# dual_encoder_i2c_shield_revB.net
KiCad netlist of a schematic drawn in EAGLE
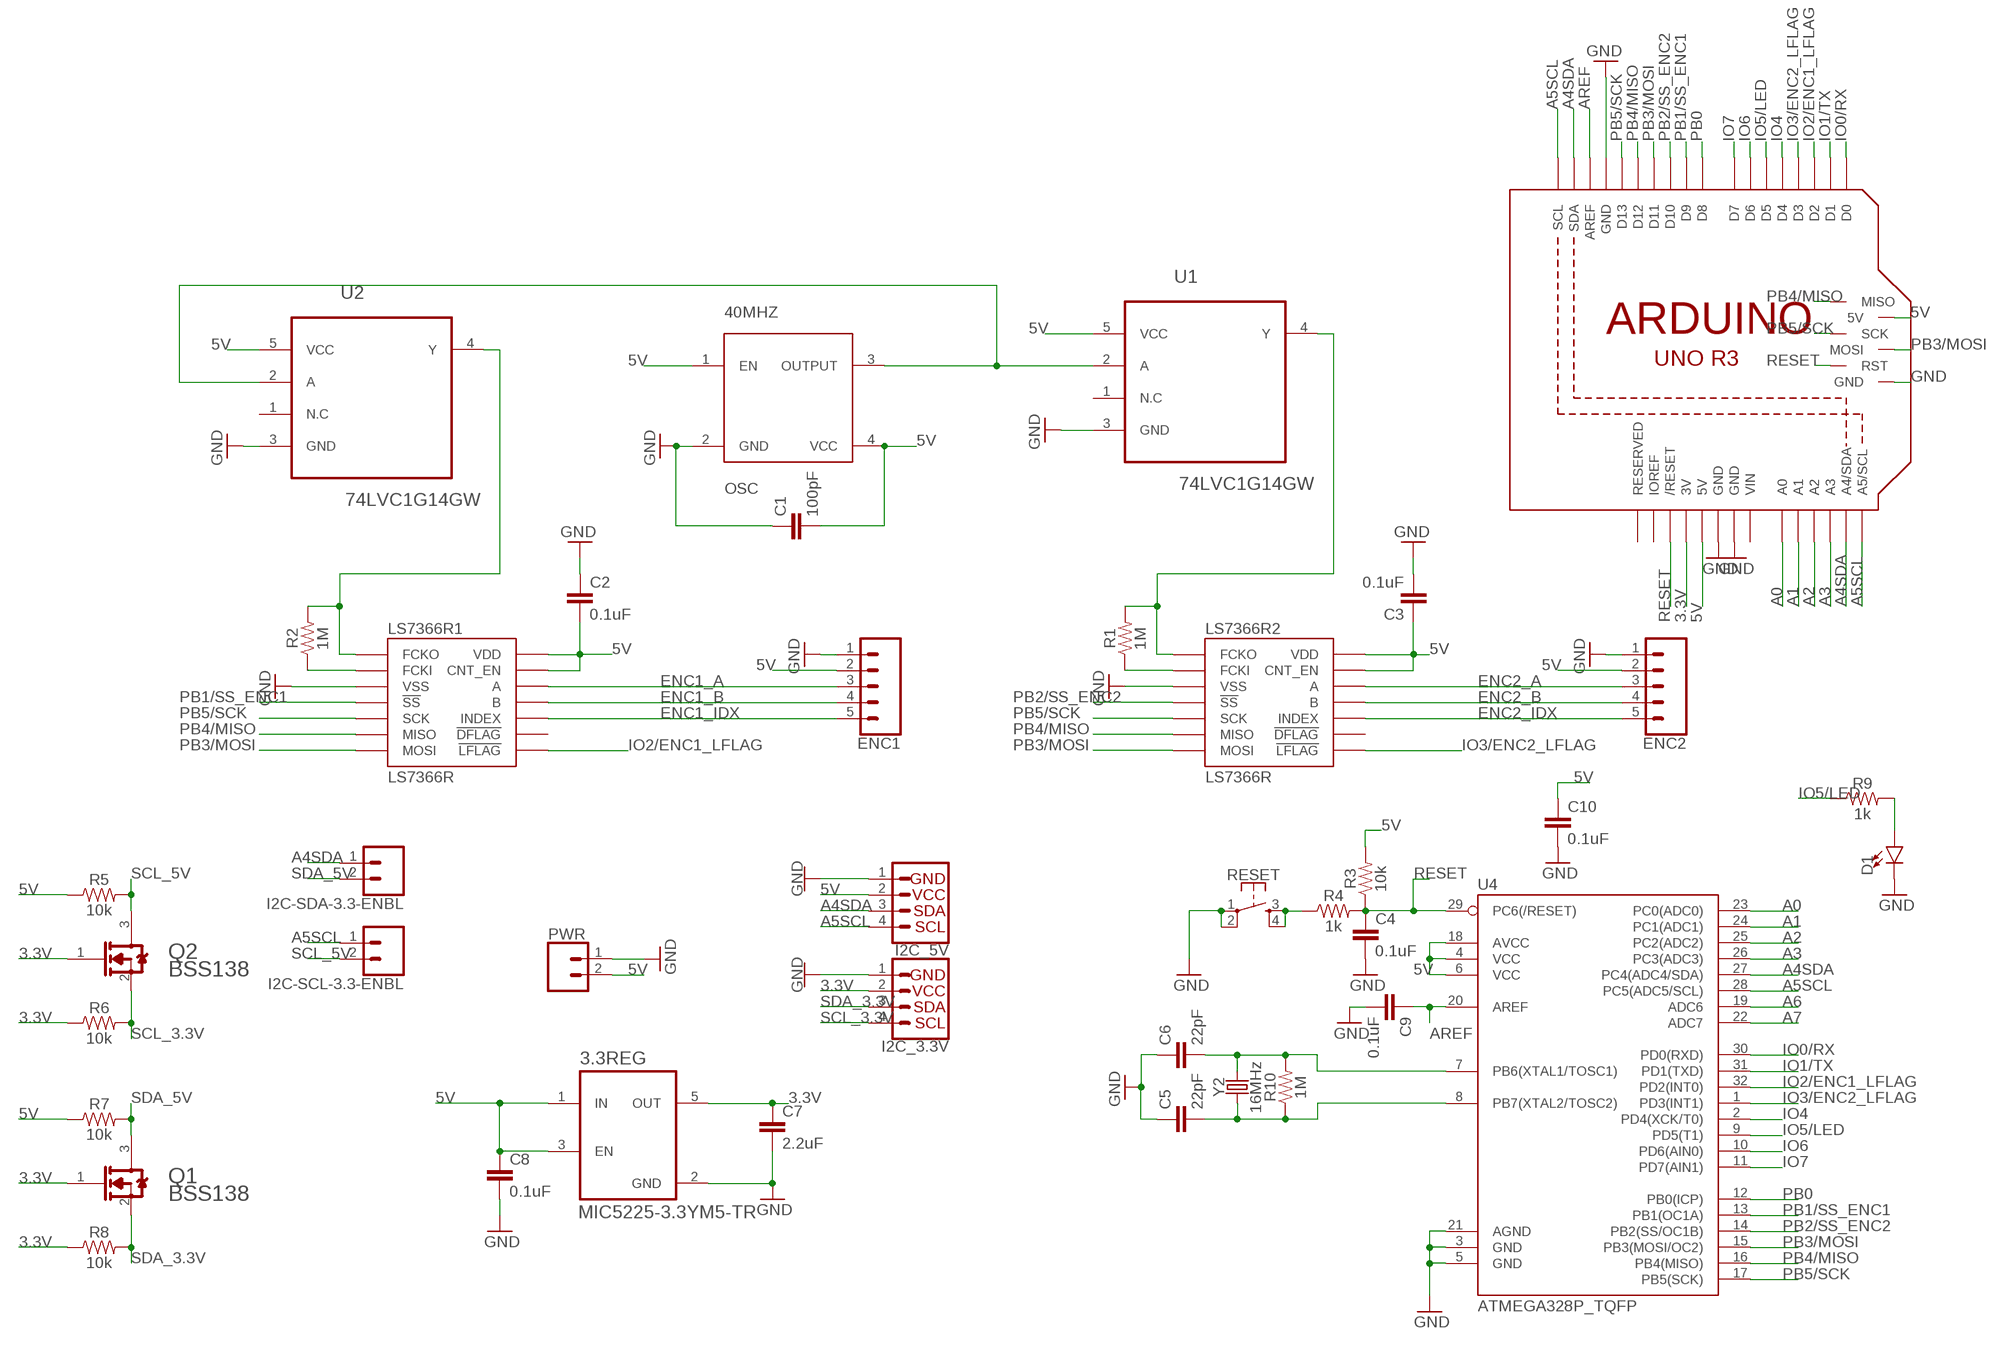
[diagram p0: schematic, sheet 1]

(export (version "E")
  (design (tool "Eeschema 10.0.6"))
  (components
    (comp (ref "3.3REG")
      (value "MIC5225-3.3YM5-TR")
      (footprint "eagle-import:SOT95P280X145-5N")
      (fields (field (name "MF") "Microchip"))
      (libsource (lib "eagle-import") (part "MIC5225-3.3YM5-TR"))
    )
    (comp (ref "40MHZ")
      (value "OSC")
      (footprint "eagle-import:CB3OSCILLATOR")
      (libsource (lib "eagle-import") (part "OSC"))
    )
    (comp (ref "C1")
      (value "100pF")
      (footprint "eagle-import:0603")
      (libsource (lib "eagle-import") (part "100PF-0603-50V-5%"))
    )
    (comp (ref "C2")
      (value "0.1uF")
      (footprint "eagle-import:0603")
      (libsource (lib "eagle-import") (part "0.1UF-0603-25V-5%"))
    )
    (comp (ref "C3")
      (value "0.1uF")
      (footprint "eagle-import:0603")
      (libsource (lib "eagle-import") (part "0.1UF-0603-25V-5%"))
    )
    (comp (ref "C4")
      (value "0.1uF")
      (footprint "eagle-import:0603")
      (libsource (lib "eagle-import") (part "0.1UF-0603-25V-5%"))
    )
    (comp (ref "C5")
      (value "22pF")
      (footprint "eagle-import:0603")
      (libsource (lib "eagle-import") (part "22PF-0603-50V-5%"))
    )
    (comp (ref "C6")
      (value "22pF")
      (footprint "eagle-import:0603")
      (libsource (lib "eagle-import") (part "22PF-0603-50V-5%"))
    )
    (comp (ref "C7")
      (value "2.2uF")
      (footprint "eagle-import:0603")
      (libsource (lib "eagle-import") (part "2.2UF-0603-10V-20%"))
    )
    (comp (ref "C8")
      (value "0.1uF")
      (footprint "eagle-import:0603")
      (libsource (lib "eagle-import") (part "0.1UF-0603-25V-5%"))
    )
    (comp (ref "C9")
      (value "0.1uF")
      (footprint "eagle-import:0603")
      (libsource (lib "eagle-import") (part "0.1UF-0603-25V-5%"))
    )
    (comp (ref "C10")
      (value "0.1uF")
      (footprint "eagle-import:0603")
      (libsource (lib "eagle-import") (part "0.1UF-0603-25V-5%"))
    )
    (comp (ref "D1")
      (value "LED0603")
      (footprint "eagle-import:LED-0603")
      (libsource (lib "eagle-import") (part "LED0603"))
    )
    (comp (ref "ENC1")
      (value "CONN_05")
      (footprint "eagle-import:1X05")
      (libsource (lib "eagle-import") (part "CONN_05"))
    )
    (comp (ref "ENC2")
      (value "CONN_05")
      (footprint "eagle-import:1X05")
      (libsource (lib "eagle-import") (part "CONN_05"))
    )
    (comp (ref "I2C-SCL-3.3-ENBL")
      (value "CONN_02")
      (footprint "eagle-import:1X02")
      (libsource (lib "eagle-import") (part "CONN_02"))
    )
    (comp (ref "I2C-SDA-3.3-ENBL")
      (value "CONN_02")
      (footprint "eagle-import:1X02")
      (libsource (lib "eagle-import") (part "CONN_02"))
    )
    (comp (ref "I2C_3.3V")
      (value "QWIIC_CONNECTORJS-1MM")
      (footprint "eagle-import:JST04_1MM_RA")
      (libsource (lib "eagle-import") (part "QWIIC_CONNECTORJS-1MM"))
    )
    (comp (ref "I2C_5V")
      (value "QWIIC_CONNECTORJS-1MM")
      (footprint "eagle-import:JST04_1MM_RA")
      (libsource (lib "eagle-import") (part "QWIIC_CONNECTORJS-1MM"))
    )
    (comp (ref "LS7366R1")
      (value "LS7366R")
      (footprint "eagle-import:SOIC14")
      (fields (field (name "MF") "LSI"))
      (libsource (lib "eagle-import") (part "LS7366R"))
    )
    (comp (ref "LS7366R2")
      (value "LS7366R")
      (footprint "eagle-import:SOIC14")
      (fields (field (name "MF") "LSI"))
      (libsource (lib "eagle-import") (part "LS7366R"))
    )
    (comp (ref "M1")
      (value "ARDUINO_R3_ICSP")
      (footprint "eagle-import:ARDUINOR3_ICSP")
      (libsource (lib "eagle-import") (part "ARDUINO_R3_ICSP"))
    )
    (comp (ref "PWR")
      (value "CONN_02-JST-2MM-SMT")
      (footprint "eagle-import:JST-2-SMD")
      (libsource (lib "eagle-import") (part "CONN_02-JST-2MM-SMT"))
    )
    (comp (ref "Q1")
      (value "ON_SEMI_BSS138ON_SEMI_BSS138_0_0")
      (footprint "eagle-import:ON_SEMI_BSS138_0")
      (fields
        (field (name "DIGIKEY_PART_NUMBER") "BSS138CT-ND")
        (field (name "MF") "ON Semi")
        (field (name "MOUSER_PART_NUMBER") "512-BSS138")
      )
      (libsource (lib "eagle-import") (part "ON_SEMI_BSS138ON_SEMI_BSS138_0_0"))
    )
    (comp (ref "Q2")
      (value "ON_SEMI_BSS138ON_SEMI_BSS138_0_0")
      (footprint "eagle-import:ON_SEMI_BSS138_0")
      (fields
        (field (name "DIGIKEY_PART_NUMBER") "BSS138CT-ND")
        (field (name "MF") "ON Semi")
        (field (name "MOUSER_PART_NUMBER") "512-BSS138")
      )
      (libsource (lib "eagle-import") (part "ON_SEMI_BSS138ON_SEMI_BSS138_0_0"))
    )
    (comp (ref "R1")
      (value "1M")
      (footprint "eagle-import:0603")
      (libsource (lib "eagle-import") (part "1MOHM-0603-1/4W-5%"))
    )
    (comp (ref "R2")
      (value "1M")
      (footprint "eagle-import:0603")
      (libsource (lib "eagle-import") (part "1MOHM-0603-1/4W-5%"))
    )
    (comp (ref "R3")
      (value "10k")
      (footprint "eagle-import:0603")
      (libsource (lib "eagle-import") (part "10KOHM-0603-1/10W-1%"))
    )
    (comp (ref "R4")
      (value "1k")
      (footprint "eagle-import:0603")
      (libsource (lib "eagle-import") (part "1KOHM-0603-1/10W-1%"))
    )
    (comp (ref "R5")
      (value "10k")
      (footprint "eagle-import:0603")
      (libsource (lib "eagle-import") (part "10KOHM-0603-1/10W-1%"))
    )
    (comp (ref "R6")
      (value "10k")
      (footprint "eagle-import:0603")
      (libsource (lib "eagle-import") (part "10KOHM-0603-1/10W-1%"))
    )
    (comp (ref "R7")
      (value "10k")
      (footprint "eagle-import:0603")
      (libsource (lib "eagle-import") (part "10KOHM-0603-1/10W-1%"))
    )
    (comp (ref "R8")
      (value "10k")
      (footprint "eagle-import:0603")
      (libsource (lib "eagle-import") (part "10KOHM-0603-1/10W-1%"))
    )
    (comp (ref "R9")
      (value "1k")
      (footprint "eagle-import:0603")
      (libsource (lib "eagle-import") (part "1KOHM-0603-1/10W-1%"))
    )
    (comp (ref "R10")
      (value "1M")
      (footprint "eagle-import:0603")
      (libsource (lib "eagle-import") (part "1MOHM-0603-1/4W-5%"))
    )
    (comp (ref "RESET")
      (value "MOMENTARY-SWITCH-SPST-2-SMD-5.2MM")
      (footprint "eagle-import:TACTILE_SWITCH_SMD_5.2MM")
      (libsource (lib "eagle-import") (part "MOMENTARY-SWITCH-SPST-2-SMD-5.2MM"))
    )
    (comp (ref "U1")
      (value "74LVC1G14GW")
      (footprint "eagle-import:SOT65P210X110-5N")
      (fields (field (name "MF") "NXP Semiconductors"))
      (libsource (lib "eagle-import") (part "74LVC1G14GW"))
    )
    (comp (ref "U2")
      (value "74LVC1G14GW")
      (footprint "eagle-import:SOT65P210X110-5N")
      (fields (field (name "MF") "NXP Semiconductors"))
      (libsource (lib "eagle-import") (part "74LVC1G14GW"))
    )
    (comp (ref "U4")
      (value "ATMEGA328P_TQFP")
      (footprint "eagle-import:TQFP32-08")
      (libsource (lib "eagle-import") (part "ATMEGA328P_TQFP"))
    )
    (comp (ref "Y2")
      (value "16MHz")
      (footprint "eagle-import:CRYSTAL-SMD-5X3.2-4PAD")
      (libsource (lib "eagle-import") (part "CRYSTAL-16MHZSMD-5X3.2"))
    )
  )
  (nets
    (net (code "1") (name "/3.3V") (class "Default")
      (node (ref "3.3REG") (pin "5") (pinfunction "OUT_5") (pintype "output"))
      (node (ref "C7") (pin "1") (pinfunction "1_1") (pintype "passive"))
      (node (ref "I2C_3.3V") (pin "2") (pinfunction "2_2") (pintype "power_in"))
      (node (ref "M1") (pin "3V") (pinfunction "3V_3V") (pintype "power_in"))
      (node (ref "Q1") (pin "1") (pinfunction "G_1") (pintype "bidirectional"))
      (node (ref "Q2") (pin "1") (pinfunction "G_1") (pintype "bidirectional"))
      (node (ref "R6") (pin "1") (pinfunction "1_1") (pintype "passive"))
      (node (ref "R8") (pin "1") (pinfunction "1_1") (pintype "passive"))
    )
    (net (code "2") (name "/5V") (class "Default")
      (node (ref "3.3REG") (pin "1") (pinfunction "IN_1") (pintype "input"))
      (node (ref "3.3REG") (pin "3") (pinfunction "EN_3") (pintype "input"))
      (node (ref "40MHZ") (pin "1") (pinfunction "EN_1") (pintype "input"))
      (node (ref "40MHZ") (pin "4") (pinfunction "VCC_4") (pintype "input"))
      (node (ref "C1") (pin "2") (pinfunction "2_2") (pintype "passive"))
      (node (ref "C10") (pin "1") (pinfunction "1_1") (pintype "passive"))
      (node (ref "C2") (pin "2") (pinfunction "2_2") (pintype "passive"))
      (node (ref "C3") (pin "1") (pinfunction "1_1") (pintype "passive"))
      (node (ref "C8") (pin "1") (pinfunction "1_1") (pintype "passive"))
      (node (ref "ENC1") (pin "2") (pinfunction "2_2") (pintype "passive"))
      (node (ref "ENC2") (pin "2") (pinfunction "2_2") (pintype "passive"))
      (node (ref "I2C_5V") (pin "2") (pinfunction "2_2") (pintype "power_in"))
      (node (ref "LS7366R1") (pin "13") (pinfunction "CNT_EN_13") (pintype "bidirectional"))
      (node (ref "LS7366R1") (pin "14") (pinfunction "VDD_14") (pintype "bidirectional"))
      (node (ref "LS7366R2") (pin "13") (pinfunction "CNT_EN_13") (pintype "bidirectional"))
      (node (ref "LS7366R2") (pin "14") (pinfunction "VDD_14") (pintype "bidirectional"))
      (node (ref "M1") (pin "5V") (pinfunction "5V_5V") (pintype "power_in"))
      (node (ref "M1") (pin "5V_ICSP") (pinfunction "5V_5V_ICSP") (pintype "passive"))
      (node (ref "PWR") (pin "2") (pinfunction "1_2") (pintype "passive"))
      (node (ref "R3") (pin "2") (pinfunction "2_2") (pintype "passive"))
      (node (ref "R5") (pin "1") (pinfunction "1_1") (pintype "passive"))
      (node (ref "R7") (pin "1") (pinfunction "1_1") (pintype "passive"))
      (node (ref "U1") (pin "5") (pinfunction "VCC_5") (pintype "power_in"))
      (node (ref "U2") (pin "5") (pinfunction "VCC_5") (pintype "power_in"))
      (node (ref "U4") (pin "18") (pinfunction "AVCC_18") (pintype "bidirectional"))
      (node (ref "U4") (pin "4") (pinfunction "VCC_4") (pintype "bidirectional"))
      (node (ref "U4") (pin "6") (pinfunction "VCC_6") (pintype "bidirectional"))
    )
    (net (code "3") (name "/A0") (class "Default")
      (node (ref "M1") (pin "A0") (pinfunction "A0_A0") (pintype "bidirectional"))
      (node (ref "U4") (pin "23") (pinfunction "PC0(ADC0)_23") (pintype "bidirectional"))
    )
    (net (code "4") (name "/A1") (class "Default")
      (node (ref "M1") (pin "A1") (pinfunction "A1_A1") (pintype "bidirectional"))
      (node (ref "U4") (pin "24") (pinfunction "PC1(ADC1)_24") (pintype "bidirectional"))
    )
    (net (code "5") (name "/A2") (class "Default")
      (node (ref "M1") (pin "A2") (pinfunction "A2_A2") (pintype "bidirectional"))
      (node (ref "U4") (pin "25") (pinfunction "PC2(ADC2)_25") (pintype "bidirectional"))
    )
    (net (code "6") (name "/A3") (class "Default")
      (node (ref "M1") (pin "A3") (pinfunction "A3_A3") (pintype "bidirectional"))
      (node (ref "U4") (pin "26") (pinfunction "PC3(ADC3)_26") (pintype "bidirectional"))
    )
    (net (code "7") (name "/A4SDA") (class "Default")
      (node (ref "I2C-SDA-3.3-ENBL") (pin "1") (pinfunction "1_1") (pintype "passive"))
      (node (ref "I2C_5V") (pin "3") (pinfunction "3_3") (pintype "passive"))
      (node (ref "M1") (pin "A4") (pinfunction "A4/SDA_A4") (pintype "bidirectional"))
      (node (ref "M1") (pin "SDA") (pinfunction "SDA_SDA") (pintype "bidirectional"))
      (node (ref "U4") (pin "27") (pinfunction "PC4(ADC4/SDA)_27") (pintype "bidirectional"))
    )
    (net (code "8") (name "/A5SCL") (class "Default")
      (node (ref "I2C-SCL-3.3-ENBL") (pin "1") (pinfunction "1_1") (pintype "passive"))
      (node (ref "I2C_5V") (pin "4") (pinfunction "4_4") (pintype "passive"))
      (node (ref "M1") (pin "A5") (pinfunction "A5/SCL_A5") (pintype "bidirectional"))
      (node (ref "M1") (pin "SCL") (pinfunction "SCL_SCL") (pintype "bidirectional"))
      (node (ref "U4") (pin "28") (pinfunction "PC5(ADC5/SCL)_28") (pintype "bidirectional"))
    )
    (net (code "9") (name "/A6") (class "Default")
      (node (ref "U4") (pin "19") (pinfunction "ADC6_19") (pintype "bidirectional"))
    )
    (net (code "10") (name "/A7") (class "Default")
      (node (ref "U4") (pin "22") (pinfunction "ADC7_22") (pintype "bidirectional"))
    )
    (net (code "11") (name "/AREF") (class "Default")
      (node (ref "C9") (pin "1") (pinfunction "1_1") (pintype "passive"))
      (node (ref "M1") (pin "AREF") (pinfunction "AREF_AREF") (pintype "bidirectional"))
      (node (ref "U4") (pin "20") (pinfunction "AREF_20") (pintype "bidirectional"))
    )
    (net (code "12") (name "/ENC1_A") (class "Default")
      (node (ref "ENC1") (pin "3") (pinfunction "3_3") (pintype "passive"))
      (node (ref "LS7366R1") (pin "12") (pinfunction "A_12") (pintype "bidirectional"))
    )
    (net (code "13") (name "/ENC1_B") (class "Default")
      (node (ref "ENC1") (pin "4") (pinfunction "4_4") (pintype "passive"))
      (node (ref "LS7366R1") (pin "11") (pinfunction "B_11") (pintype "bidirectional"))
    )
    (net (code "14") (name "/ENC1_IDX") (class "Default")
      (node (ref "ENC1") (pin "5") (pinfunction "5_5") (pintype "passive"))
      (node (ref "LS7366R1") (pin "10") (pinfunction "INDEX_10") (pintype "bidirectional"))
    )
    (net (code "15") (name "/ENC2_A") (class "Default")
      (node (ref "ENC2") (pin "3") (pinfunction "3_3") (pintype "passive"))
      (node (ref "LS7366R2") (pin "12") (pinfunction "A_12") (pintype "bidirectional"))
    )
    (net (code "16") (name "/ENC2_B") (class "Default")
      (node (ref "ENC2") (pin "4") (pinfunction "4_4") (pintype "passive"))
      (node (ref "LS7366R2") (pin "11") (pinfunction "B_11") (pintype "bidirectional"))
    )
    (net (code "17") (name "/ENC2_IDX") (class "Default")
      (node (ref "ENC2") (pin "5") (pinfunction "5_5") (pintype "passive"))
      (node (ref "LS7366R2") (pin "10") (pinfunction "INDEX_10") (pintype "bidirectional"))
    )
    (net (code "18") (name "/IO0{slash}RX") (class "Default")
      (node (ref "M1") (pin "D0") (pinfunction "D0_D0") (pintype "bidirectional"))
      (node (ref "U4") (pin "30") (pinfunction "PD0(RXD)_30") (pintype "bidirectional"))
    )
    (net (code "19") (name "/IO1{slash}TX") (class "Default")
      (node (ref "M1") (pin "D1") (pinfunction "D1_D1") (pintype "bidirectional"))
      (node (ref "U4") (pin "31") (pinfunction "PD1(TXD)_31") (pintype "bidirectional"))
    )
    (net (code "20") (name "/IO2{slash}ENC1_LFLAG") (class "Default")
      (node (ref "LS7366R1") (pin "8") (pinfunction "~{LFLAG}_8") (pintype "bidirectional"))
      (node (ref "M1") (pin "D2") (pinfunction "D2_D2") (pintype "bidirectional"))
      (node (ref "U4") (pin "32") (pinfunction "PD2(INT0)_32") (pintype "bidirectional"))
    )
    (net (code "21") (name "/IO3{slash}ENC2_LFLAG") (class "Default")
      (node (ref "LS7366R2") (pin "8") (pinfunction "~{LFLAG}_8") (pintype "bidirectional"))
      (node (ref "M1") (pin "D3") (pinfunction "D3_D3") (pintype "bidirectional"))
      (node (ref "U4") (pin "1") (pinfunction "PD3(INT1)_1") (pintype "bidirectional"))
    )
    (net (code "22") (name "/IO4") (class "Default")
      (node (ref "M1") (pin "D4") (pinfunction "D4_D4") (pintype "bidirectional"))
      (node (ref "U4") (pin "2") (pinfunction "PD4(XCK/T0)_2") (pintype "bidirectional"))
    )
    (net (code "23") (name "/IO5{slash}LED") (class "Default")
      (node (ref "M1") (pin "D5") (pinfunction "D5_D5") (pintype "bidirectional"))
      (node (ref "R9") (pin "1") (pinfunction "1_1") (pintype "passive"))
      (node (ref "U4") (pin "9") (pinfunction "PD5(T1)_9") (pintype "bidirectional"))
    )
    (net (code "24") (name "/IO6") (class "Default")
      (node (ref "M1") (pin "D6") (pinfunction "D6_D6") (pintype "bidirectional"))
      (node (ref "U4") (pin "10") (pinfunction "PD6(AIN0)_10") (pintype "bidirectional"))
    )
    (net (code "25") (name "/IO7") (class "Default")
      (node (ref "M1") (pin "D7") (pinfunction "D7_D7") (pintype "bidirectional"))
      (node (ref "U4") (pin "11") (pinfunction "PD7(AIN1)_11") (pintype "bidirectional"))
    )
    (net (code "26") (name "/PB0") (class "Default")
      (node (ref "M1") (pin "D8") (pinfunction "D8_D8") (pintype "bidirectional"))
      (node (ref "U4") (pin "12") (pinfunction "PB0(ICP)_12") (pintype "bidirectional"))
    )
    (net (code "27") (name "/PB1{slash}SS_ENC1") (class "Default")
      (node (ref "LS7366R1") (pin "4") (pinfunction "~{SS}_4") (pintype "bidirectional"))
      (node (ref "M1") (pin "D9") (pinfunction "D9_D9") (pintype "bidirectional"))
      (node (ref "U4") (pin "13") (pinfunction "PB1(OC1A)_13") (pintype "bidirectional"))
    )
    (net (code "28") (name "/PB2{slash}SS_ENC2") (class "Default")
      (node (ref "LS7366R2") (pin "4") (pinfunction "~{SS}_4") (pintype "bidirectional"))
      (node (ref "M1") (pin "D10") (pinfunction "D10_D10") (pintype "bidirectional"))
      (node (ref "U4") (pin "14") (pinfunction "PB2(SS/OC1B)_14") (pintype "bidirectional"))
    )
    (net (code "29") (name "/PB3{slash}MOSI") (class "Default")
      (node (ref "LS7366R1") (pin "7") (pinfunction "MOSI_7") (pintype "bidirectional"))
      (node (ref "LS7366R2") (pin "7") (pinfunction "MOSI_7") (pintype "bidirectional"))
      (node (ref "M1") (pin "D11") (pinfunction "D11_D11") (pintype "bidirectional"))
      (node (ref "M1") (pin "MOSI") (pinfunction "MOSI_MOSI") (pintype "passive"))
      (node (ref "U4") (pin "15") (pinfunction "PB3(MOSI/OC2)_15") (pintype "bidirectional"))
    )
    (net (code "30") (name "/PB4{slash}MISO") (class "Default")
      (node (ref "LS7366R1") (pin "6") (pinfunction "MISO_6") (pintype "bidirectional"))
      (node (ref "LS7366R2") (pin "6") (pinfunction "MISO_6") (pintype "bidirectional"))
      (node (ref "M1") (pin "D12") (pinfunction "D12_D12") (pintype "bidirectional"))
      (node (ref "M1") (pin "MISO") (pinfunction "MISO_MISO") (pintype "passive"))
      (node (ref "U4") (pin "16") (pinfunction "PB4(MISO)_16") (pintype "bidirectional"))
    )
    (net (code "31") (name "/PB5{slash}SCK") (class "Default")
      (node (ref "LS7366R1") (pin "5") (pinfunction "SCK_5") (pintype "bidirectional"))
      (node (ref "LS7366R2") (pin "5") (pinfunction "SCK_5") (pintype "bidirectional"))
      (node (ref "M1") (pin "D13") (pinfunction "D13_D13") (pintype "bidirectional"))
      (node (ref "M1") (pin "SCK") (pinfunction "SCK_SCK") (pintype "passive"))
      (node (ref "U4") (pin "17") (pinfunction "PB5(SCK)_17") (pintype "bidirectional"))
    )
    (net (code "32") (name "/RESET") (class "Default")
      (node (ref "C4") (pin "1") (pinfunction "1_1") (pintype "passive"))
      (node (ref "M1") (pin "RESET") (pinfunction "/RESET_RESET") (pintype "bidirectional"))
      (node (ref "M1") (pin "RESET_ICSP") (pinfunction "RST_RESET_ICSP") (pintype "passive"))
      (node (ref "R3") (pin "1") (pinfunction "1_1") (pintype "passive"))
      (node (ref "R4") (pin "2") (pinfunction "2_2") (pintype "passive"))
      (node (ref "U4") (pin "29") (pinfunction "PC6(/RESET)_29") (pintype "bidirectional"))
    )
    (net (code "33") (name "/SCL_3.3V") (class "Default")
      (node (ref "I2C_3.3V") (pin "4") (pinfunction "4_4") (pintype "passive"))
      (node (ref "Q2") (pin "2") (pinfunction "S_2") (pintype "bidirectional"))
      (node (ref "R6") (pin "2") (pinfunction "2_2") (pintype "passive"))
    )
    (net (code "34") (name "/SCL_5V") (class "Default")
      (node (ref "I2C-SCL-3.3-ENBL") (pin "2") (pinfunction "2_2") (pintype "passive"))
      (node (ref "Q2") (pin "3") (pinfunction "D_3") (pintype "bidirectional"))
      (node (ref "R5") (pin "2") (pinfunction "2_2") (pintype "passive"))
    )
    (net (code "35") (name "/SDA_3.3V") (class "Default")
      (node (ref "I2C_3.3V") (pin "3") (pinfunction "3_3") (pintype "passive"))
      (node (ref "Q1") (pin "2") (pinfunction "S_2") (pintype "bidirectional"))
      (node (ref "R8") (pin "2") (pinfunction "2_2") (pintype "passive"))
    )
    (net (code "36") (name "/SDA_5V") (class "Default")
      (node (ref "I2C-SDA-3.3-ENBL") (pin "2") (pinfunction "2_2") (pintype "passive"))
      (node (ref "Q1") (pin "3") (pinfunction "D_3") (pintype "bidirectional"))
      (node (ref "R7") (pin "2") (pinfunction "2_2") (pintype "passive"))
    )
    (net (code "37") (name "/VIN") (class "Default")
      (node (ref "M1") (pin "VIN") (pinfunction "VIN_VIN") (pintype "power_in"))
    )
    (net (code "38") (name "GND") (class "Default")
      (node (ref "3.3REG") (pin "2") (pinfunction "GND_2") (pintype "power_in"))
      (node (ref "40MHZ") (pin "2") (pinfunction "GND_2") (pintype "input"))
      (node (ref "C1") (pin "1") (pinfunction "1_1") (pintype "passive"))
      (node (ref "C10") (pin "2") (pinfunction "2_2") (pintype "passive"))
      (node (ref "C2") (pin "1") (pinfunction "1_1") (pintype "passive"))
      (node (ref "C3") (pin "2") (pinfunction "2_2") (pintype "passive"))
      (node (ref "C4") (pin "2") (pinfunction "2_2") (pintype "passive"))
      (node (ref "C5") (pin "1") (pinfunction "1_1") (pintype "passive"))
      (node (ref "C6") (pin "1") (pinfunction "1_1") (pintype "passive"))
      (node (ref "C7") (pin "2") (pinfunction "2_2") (pintype "passive"))
      (node (ref "C8") (pin "2") (pinfunction "2_2") (pintype "passive"))
      (node (ref "C9") (pin "2") (pinfunction "2_2") (pintype "passive"))
      (node (ref "D1") (pin "C") (pinfunction "C_C") (pintype "passive"))
      (node (ref "ENC1") (pin "1") (pinfunction "1_1") (pintype "passive"))
      (node (ref "ENC2") (pin "1") (pinfunction "1_1") (pintype "passive"))
      (node (ref "I2C_3.3V") (pin "1") (pinfunction "1_1") (pintype "power_in"))
      (node (ref "I2C_5V") (pin "1") (pinfunction "1_1") (pintype "power_in"))
      (node (ref "LS7366R1") (pin "3") (pinfunction "VSS_3") (pintype "bidirectional"))
      (node (ref "LS7366R2") (pin "3") (pinfunction "VSS_3") (pintype "bidirectional"))
      (node (ref "M1") (pin "GND") (pinfunction "GND_GND") (pintype "power_in"))
      (node (ref "M1") (pin "GND@1") (pinfunction "GND_GND@1") (pintype "power_in"))
      (node (ref "M1") (pin "GND@2") (pinfunction "GND_GND@2") (pintype "passive"))
      (node (ref "M1") (pin "GND@3") (pinfunction "GND_GND@3") (pintype "power_in"))
      (node (ref "PWR") (pin "1") (pinfunction "2_1") (pintype "passive"))
      (node (ref "RESET") (pin "1") (pinfunction "1_1") (pintype "passive"))
      (node (ref "RESET") (pin "2") (pinfunction "2_2") (pintype "passive"))
      (node (ref "U1") (pin "3") (pinfunction "GND_3") (pintype "passive"))
      (node (ref "U2") (pin "3") (pinfunction "GND_3") (pintype "passive"))
      (node (ref "U4") (pin "21") (pinfunction "AGND_21") (pintype "bidirectional"))
      (node (ref "U4") (pin "3") (pinfunction "GND_3") (pintype "bidirectional"))
      (node (ref "U4") (pin "5") (pinfunction "GND_5") (pintype "bidirectional"))
    )
    (net (code "39") (name "Net-(40MHZ-OUTPUT)") (class "Default")
      (node (ref "40MHZ") (pin "3") (pinfunction "OUTPUT_3") (pintype "output"))
      (node (ref "U1") (pin "2") (pinfunction "A_2") (pintype "input"))
      (node (ref "U2") (pin "2") (pinfunction "A_2") (pintype "input"))
    )
    (net (code "40") (name "Net-(D1-PadA)") (class "Default")
      (node (ref "D1") (pin "A") (pinfunction "A_A") (pintype "passive"))
      (node (ref "R9") (pin "2") (pinfunction "2_2") (pintype "passive"))
    )
    (net (code "41") (name "Net-(LS7366R1-FCKI)") (class "Default")
      (node (ref "LS7366R1") (pin "2") (pinfunction "FCKI_2") (pintype "bidirectional"))
      (node (ref "R2") (pin "1") (pinfunction "1_1") (pintype "passive"))
    )
    (net (code "42") (name "Net-(LS7366R1-FCKO)") (class "Default")
      (node (ref "LS7366R1") (pin "1") (pinfunction "FCKO_1") (pintype "bidirectional"))
      (node (ref "R2") (pin "2") (pinfunction "2_2") (pintype "passive"))
      (node (ref "U2") (pin "4") (pinfunction "Y_4") (pintype "output"))
    )
    (net (code "43") (name "Net-(LS7366R2-FCKI)") (class "Default")
      (node (ref "LS7366R2") (pin "2") (pinfunction "FCKI_2") (pintype "bidirectional"))
      (node (ref "R1") (pin "1") (pinfunction "1_1") (pintype "passive"))
    )
    (net (code "44") (name "Net-(LS7366R2-FCKO)") (class "Default")
      (node (ref "LS7366R2") (pin "1") (pinfunction "FCKO_1") (pintype "bidirectional"))
      (node (ref "R1") (pin "2") (pinfunction "2_2") (pintype "passive"))
      (node (ref "U1") (pin "4") (pinfunction "Y_4") (pintype "output"))
    )
    (net (code "45") (name "Net-(R4-Pad1)") (class "Default")
      (node (ref "R4") (pin "1") (pinfunction "1_1") (pintype "passive"))
      (node (ref "RESET") (pin "3") (pinfunction "3_3") (pintype "passive"))
      (node (ref "RESET") (pin "4") (pinfunction "4_4") (pintype "passive"))
    )
    (net (code "46") (name "Net-(U4-PB6(XTAL1{slash}TOSC1))") (class "Default")
      (node (ref "C6") (pin "2") (pinfunction "2_2") (pintype "passive"))
      (node (ref "R10") (pin "2") (pinfunction "2_2") (pintype "passive"))
      (node (ref "U4") (pin "7") (pinfunction "PB6(XTAL1/TOSC1)_7") (pintype "bidirectional"))
      (node (ref "Y2") (pin "3") (pinfunction "2_3") (pintype "passive"))
    )
    (net (code "47") (name "Net-(U4-PB7(XTAL2{slash}TOSC2))") (class "Default")
      (node (ref "C5") (pin "2") (pinfunction "2_2") (pintype "passive"))
      (node (ref "R10") (pin "1") (pinfunction "1_1") (pintype "passive"))
      (node (ref "U4") (pin "8") (pinfunction "PB7(XTAL2/TOSC2)_8") (pintype "bidirectional"))
      (node (ref "Y2") (pin "1") (pinfunction "1_1") (pintype "passive"))
    )
    (net (code "48") (name "unconnected-(LS7366R1-~{DFLAG}-Pad9)") (class "Default")
      (node (ref "LS7366R1") (pin "9") (pinfunction "~{DFLAG}_9") (pintype "bidirectional"))
    )
    (net (code "49") (name "unconnected-(LS7366R2-~{DFLAG}-Pad9)") (class "Default")
      (node (ref "LS7366R2") (pin "9") (pinfunction "~{DFLAG}_9") (pintype "bidirectional"))
    )
    (net (code "50") (name "unconnected-(M1-PadIOREF)") (class "Default")
      (node (ref "M1") (pin "IOREF") (pinfunction "IOREF_IOREF") (pintype "output"))
    )
    (net (code "51") (name "unconnected-(M1-PadRESERVED)") (class "Default")
      (node (ref "M1") (pin "RESERVED") (pinfunction "RESERVED_RESERVED") (pintype "no_connect"))
    )
    (net (code "52") (name "unconnected-(U1-N.C-Pad1)") (class "Default")
      (node (ref "U1") (pin "1") (pinfunction "N.C_1") (pintype "no_connect"))
    )
    (net (code "53") (name "unconnected-(U2-N.C-Pad1)") (class "Default")
      (node (ref "U2") (pin "1") (pinfunction "N.C_1") (pintype "no_connect"))
    )
  )
)
